# AIRDCR.net
KiCad netlist of a schematic drawn in EAGLE
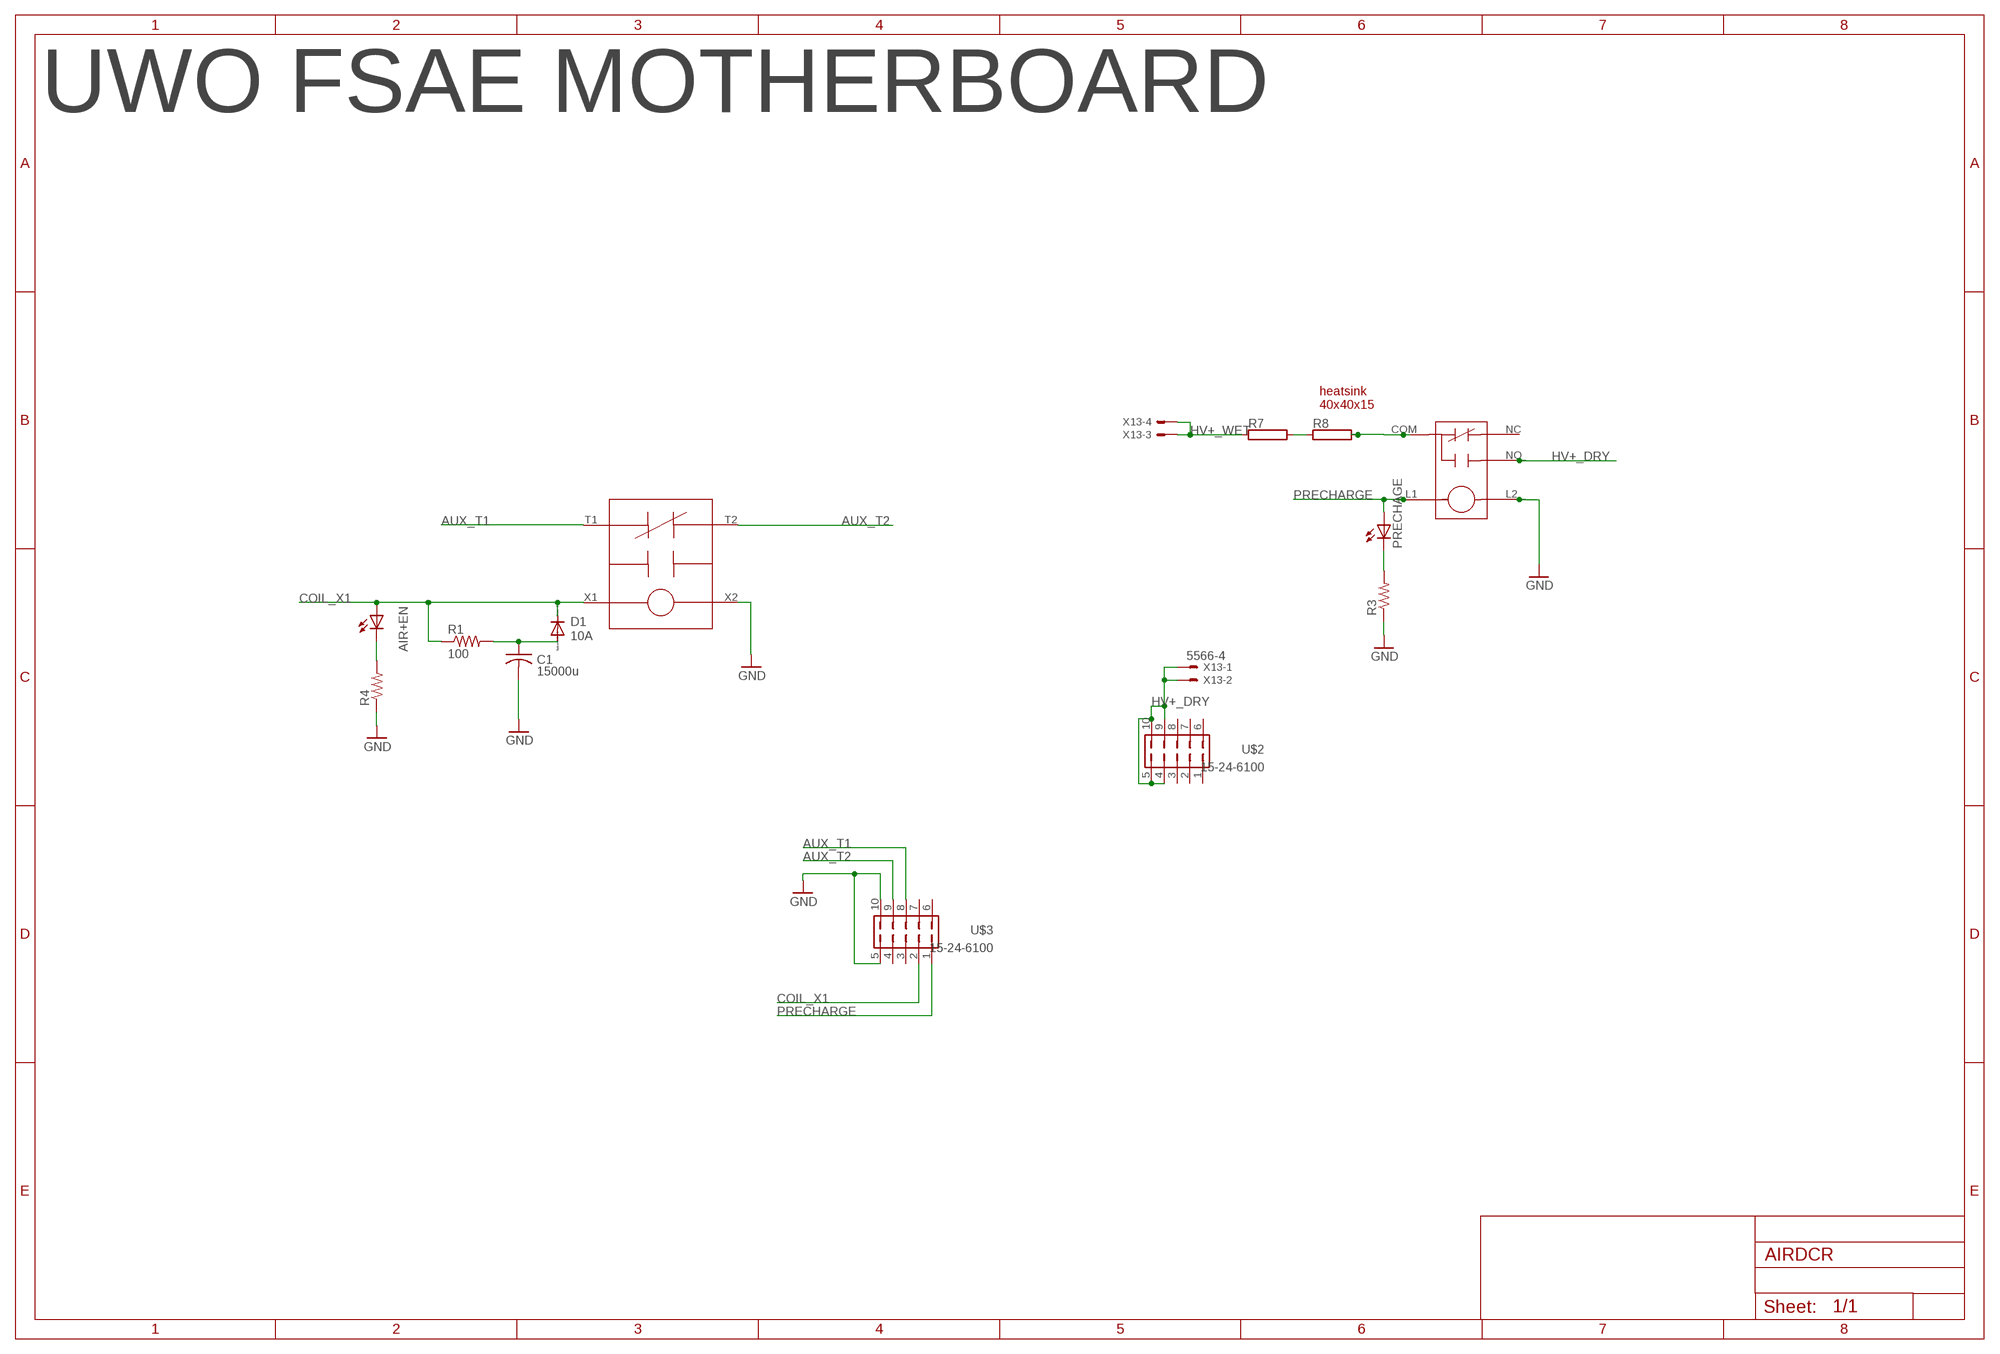
[diagram p0: schematic, sheet 1]

(export (version "E")
  (design (tool "Eeschema 10.0.6"))
  (components
    (comp (ref "AIR+EN")
      (value "LED3MM")
      (footprint "eagle-import:LED3MM")
      (libsource (lib "eagle-import") (part "LED3MM"))
    )
    (comp (ref "C1")
      (value "15000u")
      (footprint "eagle-import:CAPPRD750W65D1800H3700B")
      (libsource (lib "eagle-import") (part "AIR_HOLDUP_CAP"))
    )
    (comp (ref "D1")
      (value "10A")
      (footprint "eagle-import:DIOAD1570W120L850D500B")
      (libsource (lib "eagle-import") (part "AIR_HOLDUP_DIODE"))
    )
    (comp (ref "PRECHAGE")
      (value "LED3MM")
      (footprint "eagle-import:LED3MM")
      (libsource (lib "eagle-import") (part "LED3MM"))
    )
    (comp (ref "R1")
      (value "100")
      (footprint "eagle-import:RESAD976W63L650D250B")
      (libsource (lib "eagle-import") (part "AIR_HOLDUP_RESISTOR"))
    )
    (comp (ref "R3")
      (value "R-US_R0805")
      (footprint "eagle-import:R0805")
      (libsource (lib "eagle-import") (part "R-US_R0805"))
    )
    (comp (ref "R4")
      (value "R-US_R0805")
      (footprint "eagle-import:R0805")
      (libsource (lib "eagle-import") (part "R-US_R0805"))
    )
    (comp (ref "R7")
      (value "RMG100-H")
      (footprint "eagle-import:TO-247-2H")
      (libsource (lib "eagle-import") (part "RMG100-H"))
    )
    (comp (ref "R8")
      (value "RMG100-H")
      (footprint "eagle-import:TO-247-2H")
      (libsource (lib "eagle-import") (part "RMG100-H"))
    )
    (comp (ref "U$1")
      (value "GV224")
      (footprint "eagle-import:GV224")
      (libsource (lib "eagle-import") (part "GV224"))
    )
    (comp (ref "U$2")
      (value "15-24-6100")
      (footprint "eagle-import:15-24-6100")
      (libsource (lib "eagle-import") (part "15-24-6100"))
    )
    (comp (ref "U$3")
      (value "15-24-6100")
      (footprint "eagle-import:15-24-6100")
      (libsource (lib "eagle-import") (part "15-24-6100"))
    )
    (comp (ref "U$4")
      (value "G81C335")
      (footprint "eagle-import:G81C335")
      (libsource (lib "eagle-import") (part "G81C335"))
    )
    (comp (ref "U$8")
      (value "HEATSINK40X40X15")
      (footprint "eagle-import:HEATSINK40X40X15")
      (libsource (lib "eagle-import") (part "HEATSINK40X40X15"))
    )
    (comp (ref "X13")
      (value "5566-4")
      (footprint "eagle-import:5566-4")
      (fields (field (name "MF") "MOLEX"))
      (libsource (lib "eagle-import") (part "5566-4"))
    )
  )
  (nets
    (net (code "1") (name "/AUX_T1") (class "Default")
      (node (ref "U$1") (pin "T1") (pinfunction "T1_T1") (pintype "bidirectional"))
      (node (ref "U$3") (pin "8") (pinfunction "8_8") (pintype "passive"))
    )
    (net (code "2") (name "/AUX_T2") (class "Default")
      (node (ref "U$1") (pin "T2") (pinfunction "T2_T2") (pintype "bidirectional"))
      (node (ref "U$3") (pin "9") (pinfunction "9_9") (pintype "passive"))
    )
    (net (code "3") (name "/COIL_X1") (class "Default")
      (node (ref "AIR+EN") (pin "A") (pinfunction "A_A") (pintype "passive"))
      (node (ref "D1") (pin "1") (pinfunction "C_1") (pintype "passive"))
      (node (ref "R1") (pin "1") (pinfunction "1_1") (pintype "passive"))
      (node (ref "U$1") (pin "X1") (pinfunction "X1_X1") (pintype "bidirectional"))
      (node (ref "U$3") (pin "2") (pinfunction "2_2") (pintype "passive"))
    )
    (net (code "4") (name "/HV+_DRY") (class "Default")
      (node (ref "U$2") (pin "10") (pinfunction "10_10") (pintype "passive"))
      (node (ref "U$2") (pin "4") (pinfunction "4_4") (pintype "passive"))
      (node (ref "U$2") (pin "5") (pinfunction "5_5") (pintype "passive"))
      (node (ref "U$2") (pin "9") (pinfunction "9_9") (pintype "passive"))
      (node (ref "U$4") (pin "NO") (pinfunction "NO_NO") (pintype "bidirectional"))
      (node (ref "X13") (pin "1") (pinfunction "S_1") (pintype "passive"))
      (node (ref "X13") (pin "2") (pinfunction "S_2") (pintype "passive"))
    )
    (net (code "5") (name "/HV+_WET") (class "Default")
      (node (ref "R7") (pin "1") (pinfunction "1_1") (pintype "passive"))
      (node (ref "X13") (pin "3") (pinfunction "S_3") (pintype "passive"))
      (node (ref "X13") (pin "4") (pinfunction "S_4") (pintype "passive"))
    )
    (net (code "6") (name "/PRECHARGE") (class "Default")
      (node (ref "PRECHAGE") (pin "A") (pinfunction "A_A") (pintype "passive"))
      (node (ref "U$3") (pin "1") (pinfunction "1_1") (pintype "passive"))
      (node (ref "U$4") (pin "L1") (pinfunction "L1_L1") (pintype "bidirectional"))
    )
    (net (code "7") (name "GND") (class "Default")
      (node (ref "C1") (pin "2") (pinfunction "2_2") (pintype "passive"))
      (node (ref "R3") (pin "1") (pinfunction "1_1") (pintype "passive"))
      (node (ref "R4") (pin "1") (pinfunction "1_1") (pintype "passive"))
      (node (ref "U$1") (pin "X2") (pinfunction "X2_X2") (pintype "bidirectional"))
      (node (ref "U$3") (pin "10") (pinfunction "10_10") (pintype "passive"))
      (node (ref "U$3") (pin "5") (pinfunction "5_5") (pintype "passive"))
      (node (ref "U$4") (pin "L2") (pinfunction "L2_L2") (pintype "bidirectional"))
    )
    (net (code "8") (name "Net-(AIR+EN-C)") (class "Default")
      (node (ref "AIR+EN") (pin "K") (pinfunction "C_K") (pintype "passive"))
      (node (ref "R4") (pin "2") (pinfunction "2_2") (pintype "passive"))
    )
    (net (code "9") (name "Net-(D1-A)") (class "Default")
      (node (ref "C1") (pin "1") (pinfunction "1_1") (pintype "passive"))
      (node (ref "D1") (pin "2") (pinfunction "A_2") (pintype "passive"))
      (node (ref "R1") (pin "2") (pinfunction "2_2") (pintype "passive"))
    )
    (net (code "10") (name "Net-(PRECHAGE-C)") (class "Default")
      (node (ref "PRECHAGE") (pin "K") (pinfunction "C_K") (pintype "passive"))
      (node (ref "R3") (pin "2") (pinfunction "2_2") (pintype "passive"))
    )
    (net (code "11") (name "Net-(R7-Pad2)") (class "Default")
      (node (ref "R7") (pin "2") (pinfunction "2_2") (pintype "passive"))
      (node (ref "R8") (pin "1") (pinfunction "1_1") (pintype "passive"))
    )
    (net (code "12") (name "Net-(R8-Pad2)") (class "Default")
      (node (ref "R8") (pin "2") (pinfunction "2_2") (pintype "passive"))
      (node (ref "U$4") (pin "COM") (pinfunction "COM_COM") (pintype "bidirectional"))
    )
    (net (code "13") (name "unconnected-(U$2-Pad1)") (class "Default")
      (node (ref "U$2") (pin "1") (pinfunction "1_1") (pintype "passive"))
    )
    (net (code "14") (name "unconnected-(U$2-Pad2)") (class "Default")
      (node (ref "U$2") (pin "2") (pinfunction "2_2") (pintype "passive"))
    )
    (net (code "15") (name "unconnected-(U$2-Pad3)") (class "Default")
      (node (ref "U$2") (pin "3") (pinfunction "3_3") (pintype "passive"))
    )
    (net (code "16") (name "unconnected-(U$2-Pad6)") (class "Default")
      (node (ref "U$2") (pin "6") (pinfunction "6_6") (pintype "passive"))
    )
    (net (code "17") (name "unconnected-(U$2-Pad7)") (class "Default")
      (node (ref "U$2") (pin "7") (pinfunction "7_7") (pintype "passive"))
    )
    (net (code "18") (name "unconnected-(U$2-Pad8)") (class "Default")
      (node (ref "U$2") (pin "8") (pinfunction "8_8") (pintype "passive"))
    )
    (net (code "19") (name "unconnected-(U$3-Pad3)") (class "Default")
      (node (ref "U$3") (pin "3") (pinfunction "3_3") (pintype "passive"))
    )
    (net (code "20") (name "unconnected-(U$3-Pad4)") (class "Default")
      (node (ref "U$3") (pin "4") (pinfunction "4_4") (pintype "passive"))
    )
    (net (code "21") (name "unconnected-(U$3-Pad6)") (class "Default")
      (node (ref "U$3") (pin "6") (pinfunction "6_6") (pintype "passive"))
    )
    (net (code "22") (name "unconnected-(U$3-Pad7)") (class "Default")
      (node (ref "U$3") (pin "7") (pinfunction "7_7") (pintype "passive"))
    )
    (net (code "23") (name "unconnected-(U$4-PadNC)") (class "Default")
      (node (ref "U$4") (pin "NC") (pinfunction "NC_NC") (pintype "bidirectional"))
    )
  )
)
